# TSOC_GROVEY_ONE_R0_1.net
KiCad netlist of a schematic drawn in EAGLE
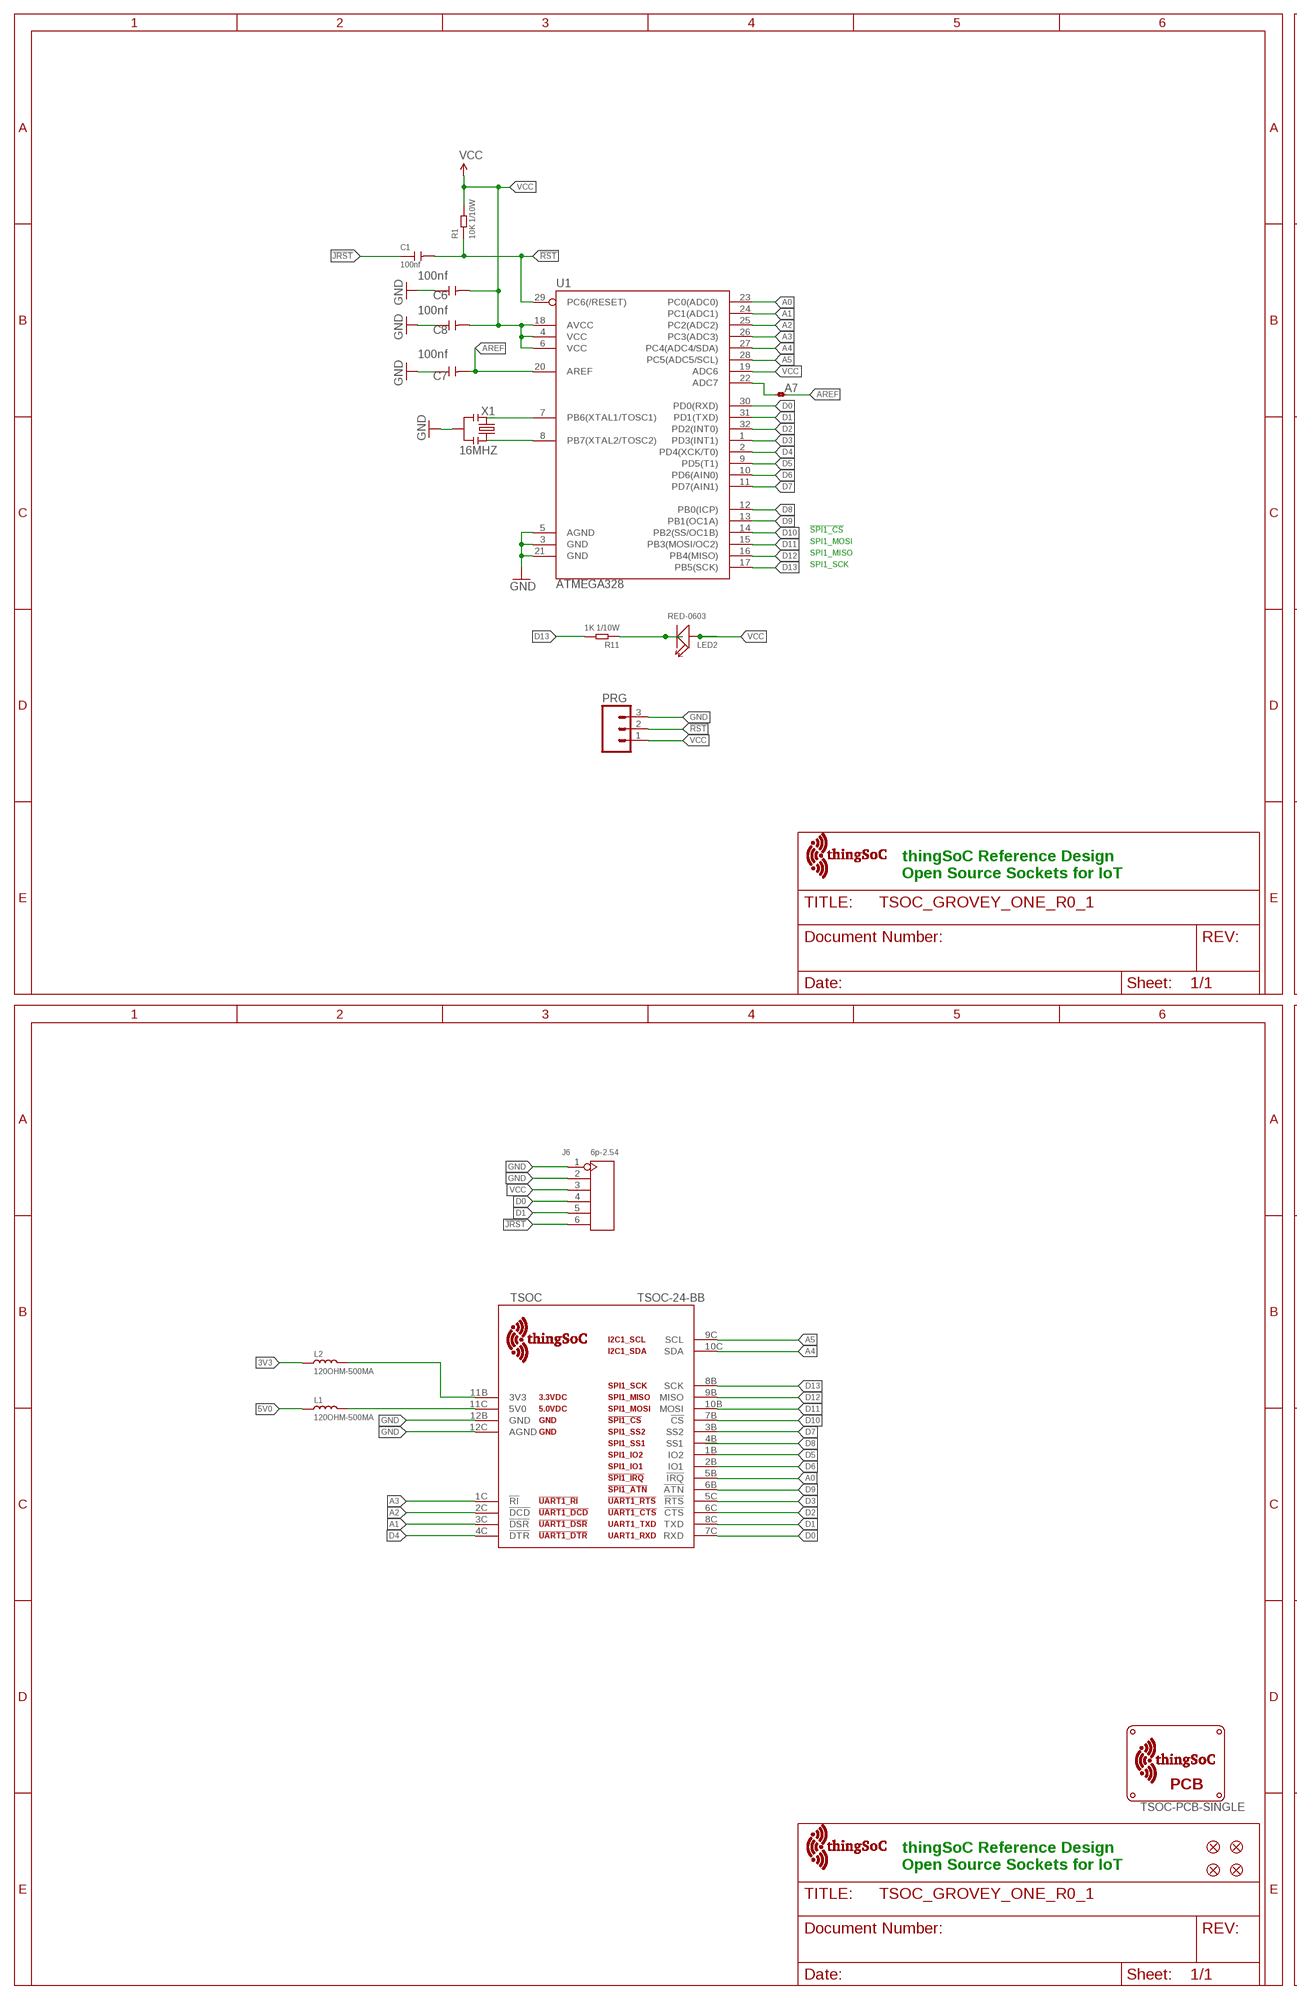
[diagram p0: schematic, sheet 1, part 1 of 2]
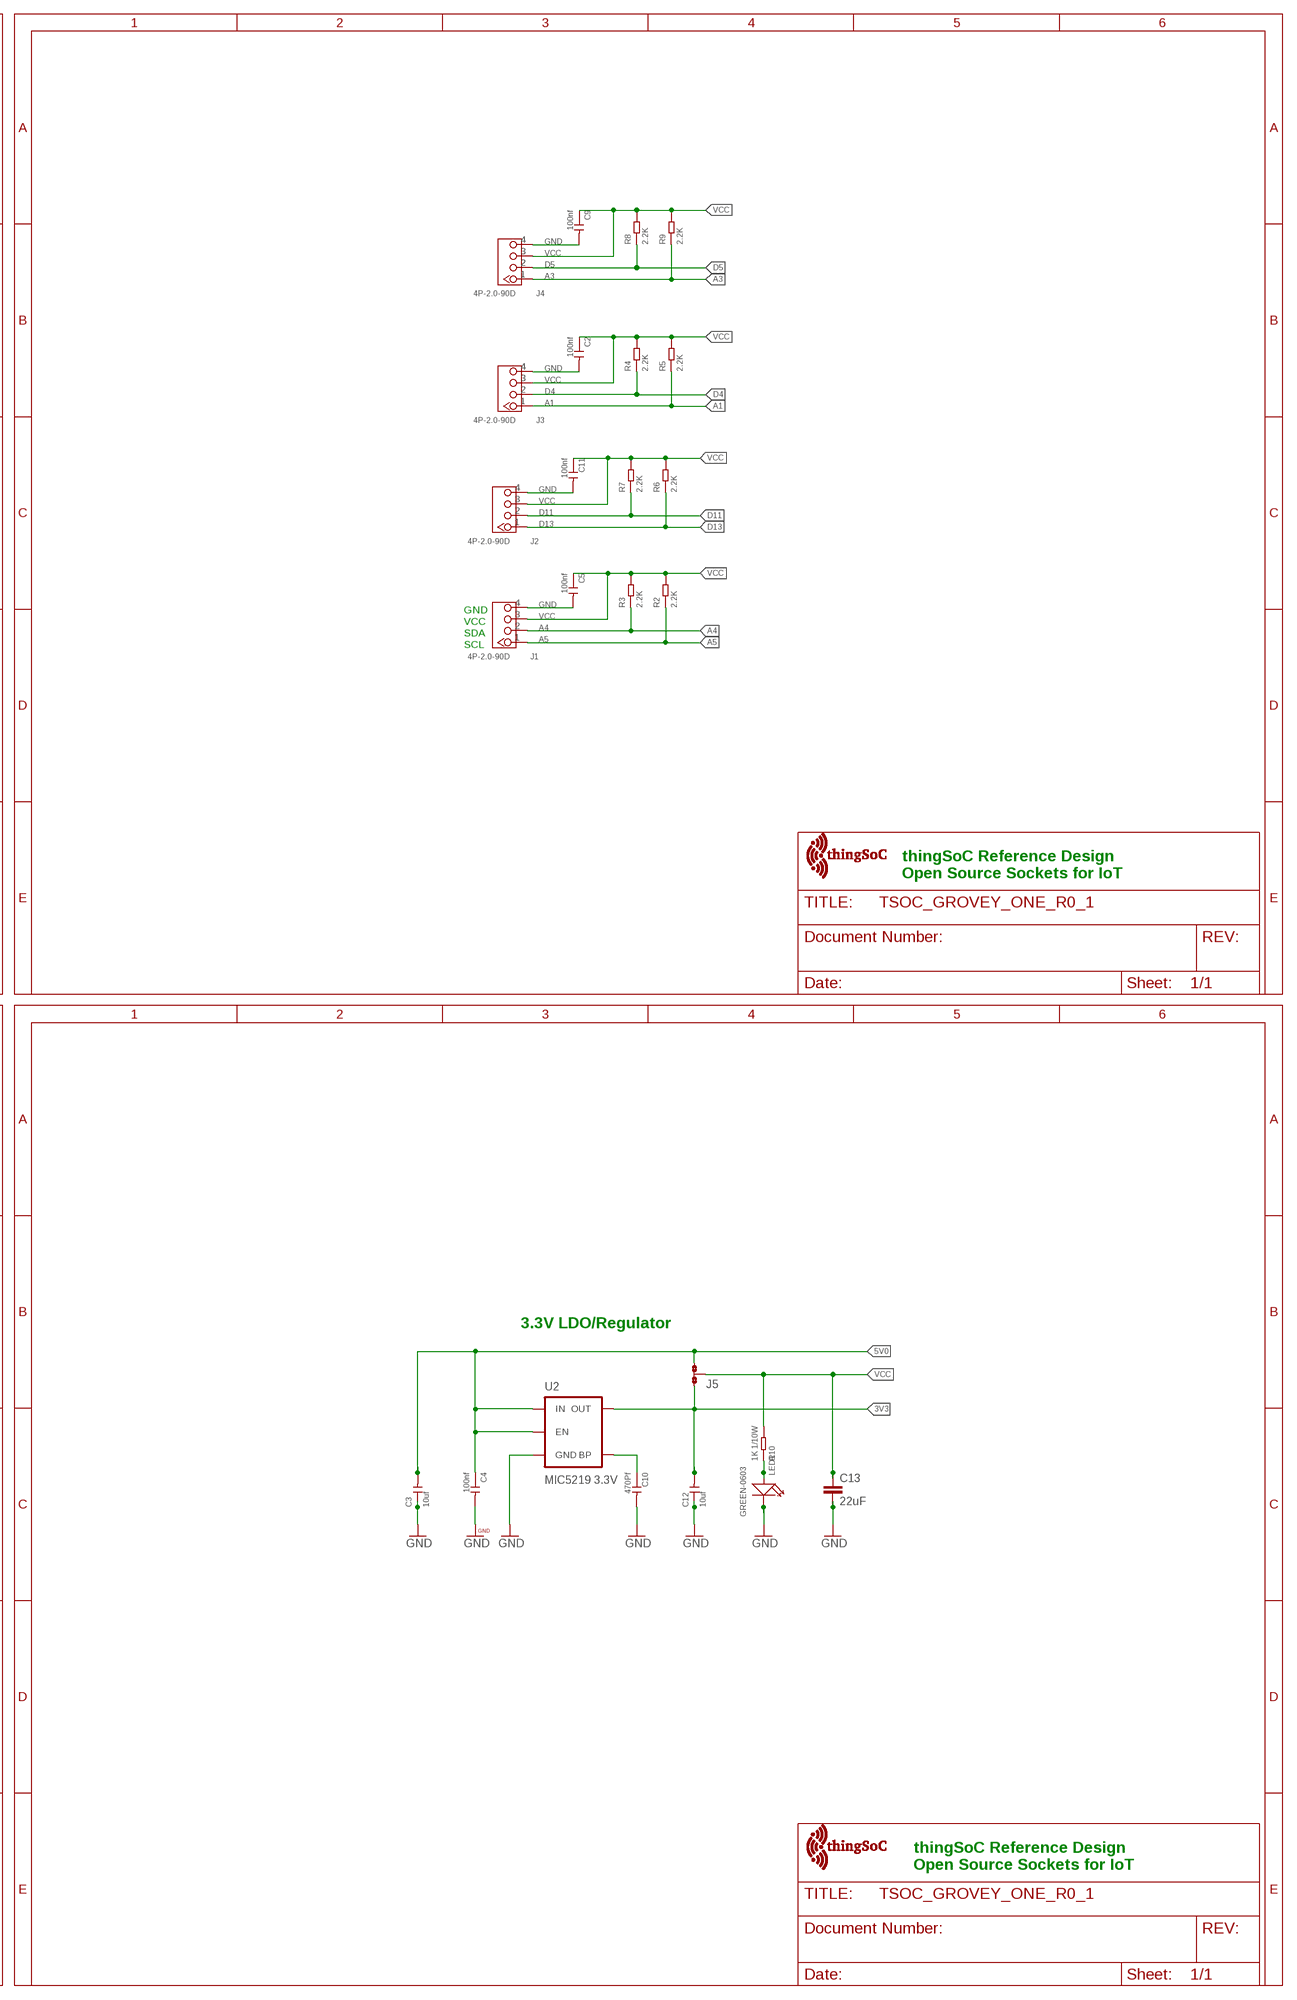
[diagram p1: schematic, sheet 1, part 2 of 2]

(export (version "E")
  (design (tool "Eeschema 10.0.6"))
  (components
    (comp (ref "$$U$2")
      (value "TSOC-PCB-SINGLE")
      (footprint "eagle-import:TSOC-BB-BRD-DIM")
      (libsource (lib "eagle-import") (part "TSOC-PCB-SINGLE"))
    )
    (comp (ref "A7")
      (value "JMP-2-NO")
      (footprint "eagle-import:JMP-2-NO")
      (libsource (lib "eagle-import") (part "JMP-2-NO"))
    )
    (comp (ref "C1")
      (value "100nf")
      (footprint "eagle-import:C0603")
      (fields (field (name "MPN") "CC0603KRX7R9BB104"))
      (libsource (lib "eagle-import") (part "CERAMIC-100NF-50V-10%-X7R(0603)"))
    )
    (comp (ref "C2")
      (value "100nf")
      (footprint "eagle-import:C0603")
      (fields (field (name "MPN") "CC0603KRX7R9BB104"))
      (libsource (lib "eagle-import") (part "CERAMIC-100NF-50V-10%-X7R(0603)"))
    )
    (comp (ref "C3")
      (value "10uf")
      (footprint "eagle-import:C0603")
      (fields (field (name "MPN") "CC0603KRX5R6BB106"))
      (libsource (lib "eagle-import") (part "CERAMIC-10UF-10V-10%-X5R(0603)"))
    )
    (comp (ref "C4")
      (value "100nf")
      (footprint "eagle-import:C0603")
      (fields (field (name "MPN") "CC0603KRX7R9BB104"))
      (libsource (lib "eagle-import") (part "CERAMIC-100NF-50V-10%-X7R(0603)"))
    )
    (comp (ref "C5")
      (value "100nf")
      (footprint "eagle-import:C0603")
      (fields (field (name "MPN") "CC0603KRX7R9BB104"))
      (libsource (lib "eagle-import") (part "CERAMIC-100NF-50V-10%-X7R(0603)"))
    )
    (comp (ref "C6")
      (value "100nf")
      (footprint "eagle-import:C0603")
      (fields (field (name "MPN") "CC0603KRX7R9BB104"))
      (libsource (lib "eagle-import") (part "CERAMIC-100NF-50V-10%-X7R(0603)"))
    )
    (comp (ref "C7")
      (value "100nf")
      (footprint "eagle-import:C0603")
      (fields (field (name "MPN") "CC0603KRX7R9BB104"))
      (libsource (lib "eagle-import") (part "CERAMIC-100NF-50V-10%-X7R(0603)"))
    )
    (comp (ref "C8")
      (value "100nf")
      (footprint "eagle-import:C0603")
      (fields (field (name "MPN") "CC0603KRX7R9BB104"))
      (libsource (lib "eagle-import") (part "CERAMIC-100NF-50V-10%-X7R(0603)"))
    )
    (comp (ref "C9")
      (value "100nf")
      (footprint "eagle-import:C0603")
      (fields (field (name "MPN") "CC0603KRX7R9BB104"))
      (libsource (lib "eagle-import") (part "CERAMIC-100NF-50V-10%-X7R(0603)"))
    )
    (comp (ref "C10")
      (value "470Pf")
      (footprint "eagle-import:C0603")
      (fields (field (name "MPN") "CC0603KRX7R9BB104"))
      (libsource (lib "eagle-import") (part "CERAMIC-100NF-50V-10%-X7R(0603)"))
    )
    (comp (ref "C11")
      (value "100nf")
      (footprint "eagle-import:C0603")
      (fields (field (name "MPN") "CC0603KRX7R9BB104"))
      (libsource (lib "eagle-import") (part "CERAMIC-100NF-50V-10%-X7R(0603)"))
    )
    (comp (ref "C12")
      (value "10uf")
      (footprint "eagle-import:C0603")
      (fields (field (name "MPN") "CC0603KRX5R6BB106"))
      (libsource (lib "eagle-import") (part "CERAMIC-10UF-10V-10%-X5R(0603)"))
    )
    (comp (ref "C13")
      (value "22uF")
      (footprint "eagle-import:EIA-1206")
      (libsource (lib "eagle-import") (part "CAP-1206"))
    )
    (comp (ref "FID1")
      (value "FIDUCIALUFIDUCIAL")
      (footprint "eagle-import:MICRO-FIDUCIAL")
      (libsource (lib "eagle-import") (part "FIDUCIALUFIDUCIAL"))
    )
    (comp (ref "FID2")
      (value "FIDUCIALUFIDUCIAL")
      (footprint "eagle-import:MICRO-FIDUCIAL")
      (libsource (lib "eagle-import") (part "FIDUCIALUFIDUCIAL"))
    )
    (comp (ref "FID3")
      (value "FIDUCIALUFIDUCIAL")
      (footprint "eagle-import:MICRO-FIDUCIAL")
      (libsource (lib "eagle-import") (part "FIDUCIALUFIDUCIAL"))
    )
    (comp (ref "FID4")
      (value "FIDUCIALUFIDUCIAL")
      (footprint "eagle-import:MICRO-FIDUCIAL")
      (libsource (lib "eagle-import") (part "FIDUCIALUFIDUCIAL"))
    )
    (comp (ref "J1")
      (value "4P-2.0-90D")
      (footprint "eagle-import:HW4-2.0-90D")
      (libsource (lib "eagle-import") (part "GROVE-CONNECTOR-DIP-90D(4P-2.0)"))
    )
    (comp (ref "J2")
      (value "4P-2.0-90D")
      (footprint "eagle-import:HW4-2.0-90D")
      (libsource (lib "eagle-import") (part "GROVE-CONNECTOR-DIP-90D(4P-2.0)"))
    )
    (comp (ref "J3")
      (value "4P-2.0-90D")
      (footprint "eagle-import:HW4-2.0-90D")
      (libsource (lib "eagle-import") (part "GROVE-CONNECTOR-DIP-90D(4P-2.0)"))
    )
    (comp (ref "J4")
      (value "4P-2.0-90D")
      (footprint "eagle-import:HW4-2.0-90D")
      (libsource (lib "eagle-import") (part "GROVE-CONNECTOR-DIP-90D(4P-2.0)"))
    )
    (comp (ref "J5")
      (value "NO")
      (footprint "eagle-import:JMP-3-NO-PTH-2.54")
      (libsource (lib "eagle-import") (part "JMP-3-NO-PTH"))
    )
    (comp (ref "J6")
      (value "6p-2.54")
      (footprint "eagle-import:H6-2.54")
      (fields (field (name "MPN") "P125-1106A1BS116A1"))
      (libsource (lib "eagle-import") (part "DIP-BLACK-MALE-HEADER(6P-2.54)"))
    )
    (comp (ref "L1")
      (value "120OHM-500MA")
      (footprint "eagle-import:L0603")
      (fields (field (name "MPN") "BLM18AG121SN1D"))
      (libsource (lib "eagle-import") (part "SMD-FERRITE-CHIP-120-OHM-500MA(0603)"))
    )
    (comp (ref "L2")
      (value "120OHM-500MA")
      (footprint "eagle-import:L0603")
      (fields (field (name "MPN") "BLM18AG121SN1D"))
      (libsource (lib "eagle-import") (part "SMD-FERRITE-CHIP-120-OHM-500MA(0603)"))
    )
    (comp (ref "LED1")
      (value "GREEN-0603")
      (footprint "eagle-import:LED-0603")
      (fields (field (name "MPN") "19-217-G7C-AN1P2-3T"))
      (libsource (lib "eagle-import") (part "SMD-LED-CLEAR-GREEN(0603)"))
    )
    (comp (ref "LED2")
      (value "RED-0603")
      (footprint "eagle-import:LED-0603")
      (fields (field (name "MPN") "19-217-G7C-AN1P2-3T"))
      (libsource (lib "eagle-import") (part "SMD-LED-CLEAR-GREEN(0603)"))
    )
    (comp (ref "PRG")
      (value "M03PTH")
      (footprint "eagle-import:1X03")
      (libsource (lib "eagle-import") (part "M03PTH"))
    )
    (comp (ref "R1")
      (value "10K 1/10W")
      (footprint "eagle-import:R0603")
      (fields (field (name "MPN") "RC0603JR-0710KL"))
      (libsource (lib "eagle-import") (part "SMD-RES-10K-5%-1/10W(0603)"))
    )
    (comp (ref "R2")
      (value "2.2K")
      (footprint "eagle-import:R0603")
      (fields (field (name "MPN") "RC0603JR-072K2L"))
      (libsource (lib "eagle-import") (part "SMD-RES-2.2K-5%-1/10W(0603)"))
    )
    (comp (ref "R3")
      (value "2.2K")
      (footprint "eagle-import:R0603")
      (fields (field (name "MPN") "RC0603JR-072K2L"))
      (libsource (lib "eagle-import") (part "SMD-RES-2.2K-5%-1/10W(0603)"))
    )
    (comp (ref "R4")
      (value "2.2K")
      (footprint "eagle-import:R0603")
      (fields (field (name "MPN") "RC0603JR-072K2L"))
      (libsource (lib "eagle-import") (part "SMD-RES-2.2K-5%-1/10W(0603)"))
    )
    (comp (ref "R5")
      (value "2.2K")
      (footprint "eagle-import:R0603")
      (fields (field (name "MPN") "RC0603JR-072K2L"))
      (libsource (lib "eagle-import") (part "SMD-RES-2.2K-5%-1/10W(0603)"))
    )
    (comp (ref "R6")
      (value "2.2K")
      (footprint "eagle-import:R0603")
      (fields (field (name "MPN") "RC0603JR-072K2L"))
      (libsource (lib "eagle-import") (part "SMD-RES-2.2K-5%-1/10W(0603)"))
    )
    (comp (ref "R7")
      (value "2.2K")
      (footprint "eagle-import:R0603")
      (fields (field (name "MPN") "RC0603JR-072K2L"))
      (libsource (lib "eagle-import") (part "SMD-RES-2.2K-5%-1/10W(0603)"))
    )
    (comp (ref "R8")
      (value "2.2K")
      (footprint "eagle-import:R0603")
      (fields (field (name "MPN") "RC0603JR-072K2L"))
      (libsource (lib "eagle-import") (part "SMD-RES-2.2K-5%-1/10W(0603)"))
    )
    (comp (ref "R9")
      (value "2.2K")
      (footprint "eagle-import:R0603")
      (fields (field (name "MPN") "RC0603JR-072K2L"))
      (libsource (lib "eagle-import") (part "SMD-RES-2.2K-5%-1/10W(0603)"))
    )
    (comp (ref "R10")
      (value "1K 1/10W")
      (footprint "eagle-import:R0603")
      (fields (field (name "MPN") "RC0603JR-071KL"))
      (libsource (lib "eagle-import") (part "SMD-RES-1K-5%-1/10W(0603)"))
    )
    (comp (ref "R11")
      (value "1K 1/10W")
      (footprint "eagle-import:R0603")
      (fields (field (name "MPN") "RC0603JR-071KL"))
      (libsource (lib "eagle-import") (part "SMD-RES-1K-5%-1/10W(0603)"))
    )
    (comp (ref "TSOC")
      (value "TSOC-24-BB")
      (footprint "eagle-import:TSOC-BB-S24")
      (libsource (lib "eagle-import") (part "TSOC-24-BB"))
    )
    (comp (ref "U$3")
      (value "TSOC-LOGO-SMALL")
      (footprint "eagle-import:TSOC-LOGO-SML")
      (libsource (lib "eagle-import") (part "TSOC-LOGO-SMALL"))
    )
    (comp (ref "U$100")
      (value "TSOC-LOGO-SMALL")
      (footprint "eagle-import:TSOC-LOGO-SML")
      (libsource (lib "eagle-import") (part "TSOC-LOGO-SMALL"))
    )
    (comp (ref "U$101")
      (value "TSOC-LOGO-LRG")
      (footprint "eagle-import:TSOC-LOGO-LRG")
      (libsource (lib "eagle-import") (part "TSOC-LOGO-LRG"))
    )
    (comp (ref "U$103")
      (value "TSOC-LOGO-SMALL")
      (footprint "eagle-import:TSOC-LOGO-SML")
      (libsource (lib "eagle-import") (part "TSOC-LOGO-SMALL"))
    )
    (comp (ref "U1")
      (value "ATMEGA328")
      (footprint "eagle-import:TQFP32-08")
      (libsource (lib "eagle-import") (part "ATMEGA168"))
    )
    (comp (ref "U2")
      (value "MIC5219 3.3V")
      (footprint "eagle-import:SOT23-5")
      (libsource (lib "eagle-import") (part "V_REG_MIC52193.3V"))
    )
    (comp (ref "X1")
      (value "16MHZ")
      (footprint "eagle-import:X3-SMD-3.6X1.3X0.8MM")
      (fields (field (name "MPN") "CSTCE16M0V53-R0"))
      (libsource (lib "eagle-import") (part "SMD-RESONATOR-16MHZ-15PF-0.5%-40R(3P-3.2X1.3MM)"))
    )
  )
  (nets
    (net (code "1") (name "/~{JRST}") (class "Default")
      (node (ref "C1") (pin "1") (pinfunction "1_1") (pintype "passive"))
      (node (ref "J6") (pin "6") (pinfunction "6_6") (pintype "bidirectional"))
    )
    (net (code "2") (name "/~{RST}") (class "Default")
      (node (ref "C1") (pin "2") (pinfunction "2_2") (pintype "passive"))
      (node (ref "PRG") (pin "2") (pinfunction "2_2") (pintype "passive"))
      (node (ref "R1") (pin "1") (pinfunction "1_1") (pintype "passive"))
      (node (ref "U1") (pin "29") (pinfunction "PC6(/RESET)_29") (pintype "bidirectional"))
    )
    (net (code "3") (name "3V3") (class "Default")
      (node (ref "C12") (pin "2") (pinfunction "2_2") (pintype "passive"))
      (node (ref "J5") (pin "1") (pinfunction "1_1") (pintype "passive"))
      (node (ref "L2") (pin "1") (pinfunction "1_1") (pintype "passive"))
      (node (ref "U2") (pin "5") (pinfunction "OUT_5") (pintype "passive"))
    )
    (net (code "4") (name "5V0") (class "Default")
      (node (ref "C3") (pin "2") (pinfunction "2_2") (pintype "passive"))
      (node (ref "C4") (pin "1") (pinfunction "1_1") (pintype "passive"))
      (node (ref "J5") (pin "3") (pinfunction "3_3") (pintype "passive"))
      (node (ref "L1") (pin "1") (pinfunction "1_1") (pintype "passive"))
      (node (ref "U2") (pin "1") (pinfunction "IN_1") (pintype "input"))
      (node (ref "U2") (pin "3") (pinfunction "EN_3") (pintype "input"))
    )
    (net (code "5") (name "A0") (class "Default")
      (node (ref "TSOC") (pin "5B") (pinfunction "~{IRQ}_5B") (pintype "bidirectional"))
      (node (ref "U1") (pin "23") (pinfunction "PC0(ADC0)_23") (pintype "bidirectional"))
    )
    (net (code "6") (name "A1") (class "Default")
      (node (ref "J3") (pin "1") (pinfunction "1_1") (pintype "bidirectional"))
      (node (ref "R5") (pin "1") (pinfunction "1_1") (pintype "passive"))
      (node (ref "TSOC") (pin "3C") (pinfunction "~{DSR}_3C") (pintype "bidirectional"))
      (node (ref "U1") (pin "24") (pinfunction "PC1(ADC1)_24") (pintype "bidirectional"))
    )
    (net (code "7") (name "A2") (class "Default")
      (node (ref "TSOC") (pin "2C") (pinfunction "~{DCD}_2C") (pintype "bidirectional"))
      (node (ref "U1") (pin "25") (pinfunction "PC2(ADC2)_25") (pintype "bidirectional"))
    )
    (net (code "8") (name "A3") (class "Default")
      (node (ref "J4") (pin "1") (pinfunction "1_1") (pintype "bidirectional"))
      (node (ref "R9") (pin "1") (pinfunction "1_1") (pintype "passive"))
      (node (ref "TSOC") (pin "1C") (pinfunction "~{RI}_1C") (pintype "bidirectional"))
      (node (ref "U1") (pin "26") (pinfunction "PC3(ADC3)_26") (pintype "bidirectional"))
    )
    (net (code "9") (name "A4") (class "Default")
      (node (ref "J1") (pin "2") (pinfunction "2_2") (pintype "bidirectional"))
      (node (ref "R3") (pin "1") (pinfunction "1_1") (pintype "passive"))
      (node (ref "TSOC") (pin "10C") (pinfunction "SDA_10C") (pintype "bidirectional"))
      (node (ref "U1") (pin "27") (pinfunction "PC4(ADC4/SDA)_27") (pintype "bidirectional"))
    )
    (net (code "10") (name "A5") (class "Default")
      (node (ref "J1") (pin "1") (pinfunction "1_1") (pintype "bidirectional"))
      (node (ref "R2") (pin "1") (pinfunction "1_1") (pintype "passive"))
      (node (ref "TSOC") (pin "9C") (pinfunction "SCL_9C") (pintype "bidirectional"))
      (node (ref "U1") (pin "28") (pinfunction "PC5(ADC5/SCL)_28") (pintype "bidirectional"))
    )
    (net (code "11") (name "AREF") (class "Default")
      (node (ref "A7") (pin "2") (pinfunction "2_2") (pintype "passive"))
      (node (ref "C7") (pin "2") (pinfunction "2_2") (pintype "passive"))
      (node (ref "U1") (pin "20") (pinfunction "AREF_20") (pintype "bidirectional"))
    )
    (net (code "12") (name "D0") (class "Default")
      (node (ref "J6") (pin "4") (pinfunction "4_4") (pintype "bidirectional"))
      (node (ref "TSOC") (pin "7C") (pinfunction "RXD_7C") (pintype "bidirectional"))
      (node (ref "U1") (pin "30") (pinfunction "PD0(RXD)_30") (pintype "bidirectional"))
    )
    (net (code "13") (name "D1") (class "Default")
      (node (ref "J6") (pin "5") (pinfunction "5_5") (pintype "bidirectional"))
      (node (ref "TSOC") (pin "8C") (pinfunction "TXD_8C") (pintype "bidirectional"))
      (node (ref "U1") (pin "31") (pinfunction "PD1(TXD)_31") (pintype "bidirectional"))
    )
    (net (code "14") (name "D2") (class "Default")
      (node (ref "TSOC") (pin "6C") (pinfunction "~{CTS}_6C") (pintype "bidirectional"))
      (node (ref "U1") (pin "32") (pinfunction "PD2(INT0)_32") (pintype "bidirectional"))
    )
    (net (code "15") (name "D3") (class "Default")
      (node (ref "TSOC") (pin "5C") (pinfunction "~{RTS}_5C") (pintype "bidirectional"))
      (node (ref "U1") (pin "1") (pinfunction "PD3(INT1)_1") (pintype "bidirectional"))
    )
    (net (code "16") (name "D4") (class "Default")
      (node (ref "J3") (pin "2") (pinfunction "2_2") (pintype "bidirectional"))
      (node (ref "R4") (pin "1") (pinfunction "1_1") (pintype "passive"))
      (node (ref "TSOC") (pin "4C") (pinfunction "~{DTR}_4C") (pintype "bidirectional"))
      (node (ref "U1") (pin "2") (pinfunction "PD4(XCK/T0)_2") (pintype "bidirectional"))
    )
    (net (code "17") (name "D5") (class "Default")
      (node (ref "J4") (pin "2") (pinfunction "2_2") (pintype "bidirectional"))
      (node (ref "R8") (pin "1") (pinfunction "1_1") (pintype "passive"))
      (node (ref "TSOC") (pin "1B") (pinfunction "IO2_1B") (pintype "bidirectional"))
      (node (ref "U1") (pin "9") (pinfunction "PD5(T1)_9") (pintype "bidirectional"))
    )
    (net (code "18") (name "D6") (class "Default")
      (node (ref "TSOC") (pin "2B") (pinfunction "IO1_2B") (pintype "bidirectional"))
      (node (ref "U1") (pin "10") (pinfunction "PD6(AIN0)_10") (pintype "bidirectional"))
    )
    (net (code "19") (name "D7") (class "Default")
      (node (ref "TSOC") (pin "3B") (pinfunction "SS2_3B") (pintype "bidirectional"))
      (node (ref "U1") (pin "11") (pinfunction "PD7(AIN1)_11") (pintype "bidirectional"))
    )
    (net (code "20") (name "D8") (class "Default")
      (node (ref "TSOC") (pin "4B") (pinfunction "SS1_4B") (pintype "bidirectional"))
      (node (ref "U1") (pin "12") (pinfunction "PB0(ICP)_12") (pintype "bidirectional"))
    )
    (net (code "21") (name "D9") (class "Default")
      (node (ref "TSOC") (pin "6B") (pinfunction "~{ATN}_6B") (pintype "bidirectional"))
      (node (ref "U1") (pin "13") (pinfunction "PB1(OC1A)_13") (pintype "bidirectional"))
    )
    (net (code "22") (name "D10") (class "Default")
      (node (ref "TSOC") (pin "7B") (pinfunction "~{CS}_7B") (pintype "bidirectional"))
      (node (ref "U1") (pin "14") (pinfunction "PB2(SS/OC1B)_14") (pintype "bidirectional"))
    )
    (net (code "23") (name "D11") (class "Default")
      (node (ref "J2") (pin "2") (pinfunction "2_2") (pintype "bidirectional"))
      (node (ref "R7") (pin "1") (pinfunction "1_1") (pintype "passive"))
      (node (ref "TSOC") (pin "10B") (pinfunction "MOSI_10B") (pintype "bidirectional"))
      (node (ref "U1") (pin "15") (pinfunction "PB3(MOSI/OC2)_15") (pintype "bidirectional"))
    )
    (net (code "24") (name "D12") (class "Default")
      (node (ref "TSOC") (pin "9B") (pinfunction "MISO_9B") (pintype "bidirectional"))
      (node (ref "U1") (pin "16") (pinfunction "PB4(MISO)_16") (pintype "bidirectional"))
    )
    (net (code "25") (name "D13") (class "Default")
      (node (ref "J2") (pin "1") (pinfunction "1_1") (pintype "bidirectional"))
      (node (ref "R11") (pin "2") (pinfunction "2_2") (pintype "passive"))
      (node (ref "R6") (pin "1") (pinfunction "1_1") (pintype "passive"))
      (node (ref "TSOC") (pin "8B") (pinfunction "SCK_8B") (pintype "bidirectional"))
      (node (ref "U1") (pin "17") (pinfunction "PB5(SCK)_17") (pintype "bidirectional"))
    )
    (net (code "26") (name "GND") (class "Default")
      (node (ref "C10") (pin "2") (pinfunction "2_2") (pintype "passive"))
      (node (ref "C11") (pin "2") (pinfunction "2_2") (pintype "passive"))
      (node (ref "C12") (pin "1") (pinfunction "1_1") (pintype "passive"))
      (node (ref "C13") (pin "2") (pinfunction "2_2") (pintype "passive"))
      (node (ref "C2") (pin "2") (pinfunction "2_2") (pintype "passive"))
      (node (ref "C3") (pin "1") (pinfunction "1_1") (pintype "passive"))
      (node (ref "C4") (pin "2") (pinfunction "2_2") (pintype "passive"))
      (node (ref "C5") (pin "2") (pinfunction "2_2") (pintype "passive"))
      (node (ref "C6") (pin "1") (pinfunction "1_1") (pintype "passive"))
      (node (ref "C7") (pin "1") (pinfunction "1_1") (pintype "passive"))
      (node (ref "C8") (pin "1") (pinfunction "1_1") (pintype "passive"))
      (node (ref "C9") (pin "2") (pinfunction "2_2") (pintype "passive"))
      (node (ref "J1") (pin "4") (pinfunction "4_4") (pintype "bidirectional"))
      (node (ref "J2") (pin "4") (pinfunction "4_4") (pintype "bidirectional"))
      (node (ref "J3") (pin "4") (pinfunction "4_4") (pintype "bidirectional"))
      (node (ref "J4") (pin "4") (pinfunction "4_4") (pintype "bidirectional"))
      (node (ref "J6") (pin "1") (pinfunction "1_1") (pintype "bidirectional"))
      (node (ref "J6") (pin "2") (pinfunction "2_2") (pintype "bidirectional"))
      (node (ref "LED1") (pin "-") (pinfunction "-_-") (pintype "passive"))
      (node (ref "PRG") (pin "3") (pinfunction "3_3") (pintype "passive"))
      (node (ref "TSOC") (pin "12B") (pinfunction "GND_12B") (pintype "bidirectional"))
      (node (ref "TSOC") (pin "12C") (pinfunction "AGND_12C") (pintype "bidirectional"))
      (node (ref "U1") (pin "21") (pinfunction "GND_21") (pintype "bidirectional"))
      (node (ref "U1") (pin "3") (pinfunction "GND_3") (pintype "bidirectional"))
      (node (ref "U1") (pin "5") (pinfunction "AGND_5") (pintype "bidirectional"))
      (node (ref "U2") (pin "2") (pinfunction "GND_2") (pintype "input"))
      (node (ref "X1") (pin "2") (pinfunction "2_2") (pintype "passive"))
    )
    (net (code "27") (name "Net-(LED1-Pad+)") (class "Default")
      (node (ref "LED1") (pin "+") (pinfunction "+_+") (pintype "passive"))
      (node (ref "R10") (pin "1") (pinfunction "1_1") (pintype "passive"))
    )
    (net (code "28") (name "Net-(LED2-Pad-)") (class "Default")
      (node (ref "LED2") (pin "-") (pinfunction "-_-") (pintype "passive"))
      (node (ref "R11") (pin "1") (pinfunction "1_1") (pintype "passive"))
    )
    (net (code "29") (name "Net-(TSOC-3V3)") (class "Default")
      (node (ref "L2") (pin "2") (pinfunction "2_2") (pintype "passive"))
      (node (ref "TSOC") (pin "11B") (pinfunction "3V3_11B") (pintype "bidirectional"))
    )
    (net (code "30") (name "Net-(TSOC-5V0)") (class "Default")
      (node (ref "L1") (pin "2") (pinfunction "2_2") (pintype "passive"))
      (node (ref "TSOC") (pin "11C") (pinfunction "5V0_11C") (pintype "bidirectional"))
    )
    (net (code "31") (name "Net-(U1-ADC7)") (class "Default")
      (node (ref "A7") (pin "1") (pinfunction "1_1") (pintype "passive"))
      (node (ref "U1") (pin "22") (pinfunction "ADC7_22") (pintype "bidirectional"))
    )
    (net (code "32") (name "Net-(U1-PB6(XTAL1{slash}TOSC1))") (class "Default")
      (node (ref "U1") (pin "7") (pinfunction "PB6(XTAL1/TOSC1)_7") (pintype "bidirectional"))
      (node (ref "X1") (pin "3") (pinfunction "3_3") (pintype "passive"))
    )
    (net (code "33") (name "Net-(U1-PB7(XTAL2{slash}TOSC2))") (class "Default")
      (node (ref "U1") (pin "8") (pinfunction "PB7(XTAL2/TOSC2)_8") (pintype "bidirectional"))
      (node (ref "X1") (pin "1") (pinfunction "1_1") (pintype "passive"))
    )
    (net (code "34") (name "Net-(U2-BP)") (class "Default")
      (node (ref "C10") (pin "1") (pinfunction "1_1") (pintype "passive"))
      (node (ref "U2") (pin "4") (pinfunction "BP_4") (pintype "input"))
    )
    (net (code "35") (name "VCC") (class "Default")
      (node (ref "C11") (pin "1") (pinfunction "1_1") (pintype "passive"))
      (node (ref "C13") (pin "1") (pinfunction "1_1") (pintype "passive"))
      (node (ref "C2") (pin "1") (pinfunction "1_1") (pintype "passive"))
      (node (ref "C5") (pin "1") (pinfunction "1_1") (pintype "passive"))
      (node (ref "C6") (pin "2") (pinfunction "2_2") (pintype "passive"))
      (node (ref "C8") (pin "2") (pinfunction "2_2") (pintype "passive"))
      (node (ref "C9") (pin "1") (pinfunction "1_1") (pintype "passive"))
      (node (ref "J1") (pin "3") (pinfunction "3_3") (pintype "bidirectional"))
      (node (ref "J2") (pin "3") (pinfunction "3_3") (pintype "bidirectional"))
      (node (ref "J3") (pin "3") (pinfunction "3_3") (pintype "bidirectional"))
      (node (ref "J4") (pin "3") (pinfunction "3_3") (pintype "bidirectional"))
      (node (ref "J5") (pin "2") (pinfunction "2_2") (pintype "passive"))
      (node (ref "J6") (pin "3") (pinfunction "3_3") (pintype "bidirectional"))
      (node (ref "LED2") (pin "+") (pinfunction "+_+") (pintype "passive"))
      (node (ref "PRG") (pin "1") (pinfunction "1_1") (pintype "passive"))
      (node (ref "R1") (pin "2") (pinfunction "2_2") (pintype "passive"))
      (node (ref "R10") (pin "2") (pinfunction "2_2") (pintype "passive"))
      (node (ref "R2") (pin "2") (pinfunction "2_2") (pintype "passive"))
      (node (ref "R3") (pin "2") (pinfunction "2_2") (pintype "passive"))
      (node (ref "R4") (pin "2") (pinfunction "2_2") (pintype "passive"))
      (node (ref "R5") (pin "2") (pinfunction "2_2") (pintype "passive"))
      (node (ref "R6") (pin "2") (pinfunction "2_2") (pintype "passive"))
      (node (ref "R7") (pin "2") (pinfunction "2_2") (pintype "passive"))
      (node (ref "R8") (pin "2") (pinfunction "2_2") (pintype "passive"))
      (node (ref "R9") (pin "2") (pinfunction "2_2") (pintype "passive"))
      (node (ref "U1") (pin "18") (pinfunction "AVCC_18") (pintype "bidirectional"))
      (node (ref "U1") (pin "19") (pinfunction "ADC6_19") (pintype "bidirectional"))
      (node (ref "U1") (pin "4") (pinfunction "VCC_4") (pintype "bidirectional"))
      (node (ref "U1") (pin "6") (pinfunction "VCC_6") (pintype "bidirectional"))
    )
  )
)
